# ET-USB.net
KiCad netlist of a schematic drawn in Altium Designer
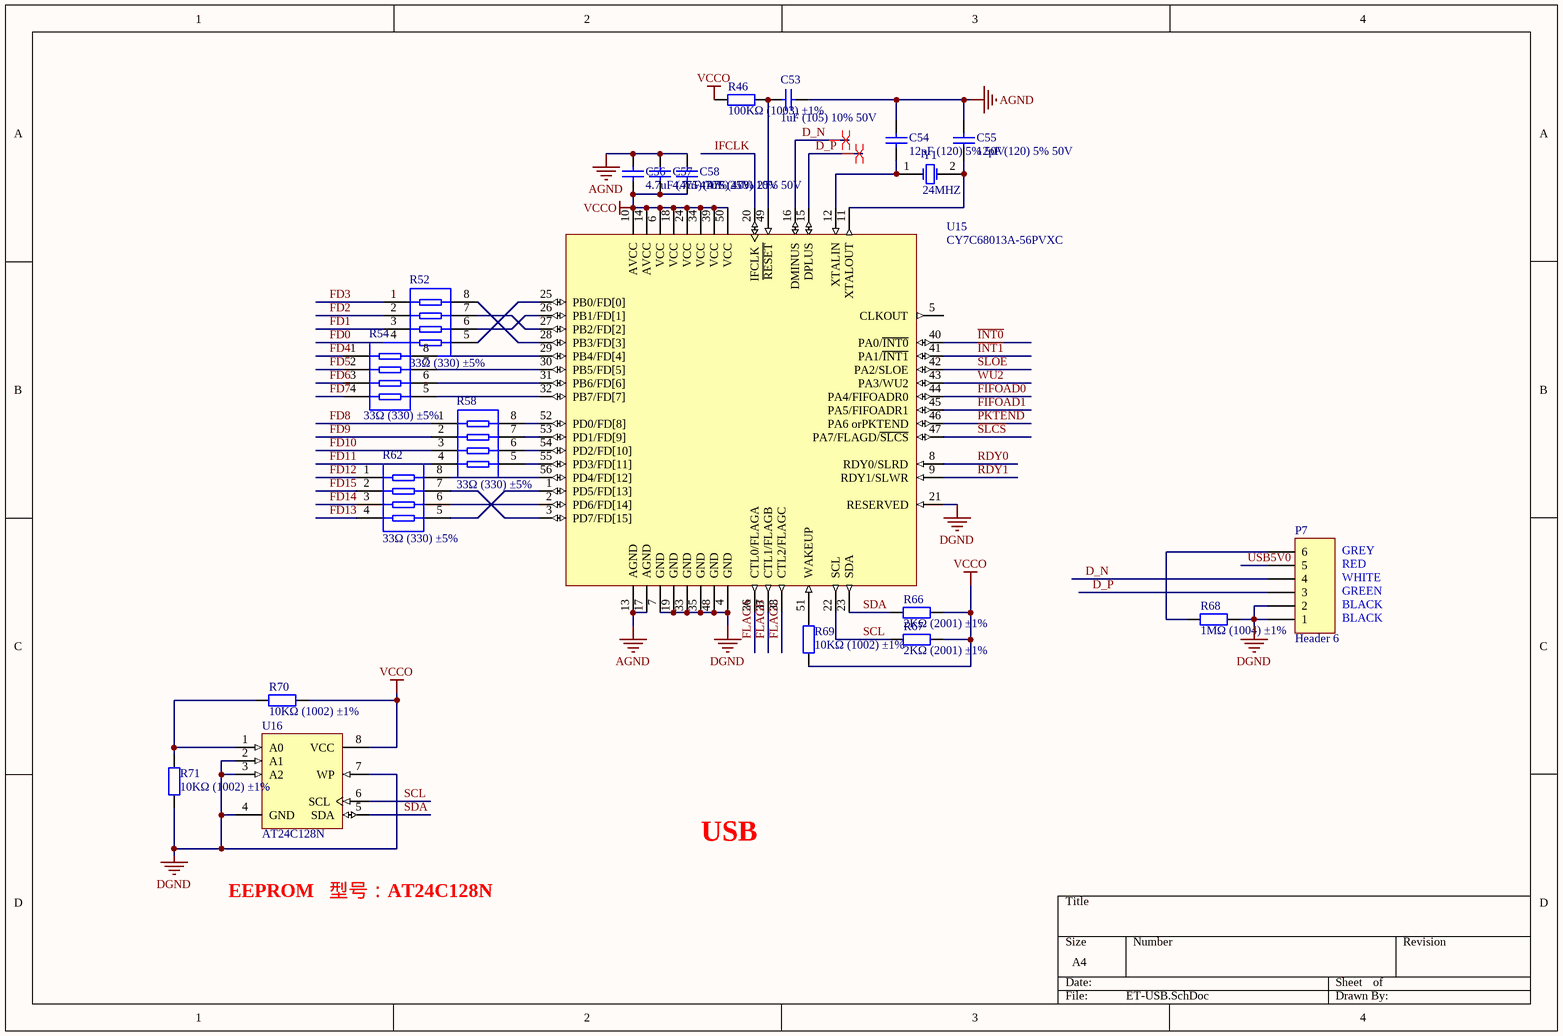
[diagram p0: ET-USB.SchDoc]

(export (version "E")
  (design (tool "Eeschema 10.0.6"))
  (components
    (comp (ref "C53")
      (value "1uF (105) 10% 50V")
      (footprint "LC-0805_C")
      (description "贴片电容")
      (libsource (lib "Miscellaneous Devices LC") (part "0805 1uF (105) 10% 50V"))
    )
    (comp (ref "C54")
      (value "12pF (120) 5% 50V")
      (footprint "LC-0805_C")
      (description "贴片电容")
      (libsource (lib "Miscellaneous Devices LC") (part "0805 12pF (120) 5% 50V"))
    )
    (comp (ref "C55")
      (value "12pF (120) 5% 50V")
      (footprint "LC-0805_C")
      (description "贴片电容")
      (libsource (lib "Miscellaneous Devices LC") (part "0805 12pF (120) 5% 50V"))
    )
    (comp (ref "C56")
      (value "4.7uF (475) 10% 25V")
      (footprint "LC-0805_C")
      (description "贴片电容")
      (libsource (lib "Miscellaneous Devices LC") (part "0805 4.7uF (475) 10% 25V"))
    )
    (comp (ref "C57")
      (value "4.7uF (475) 10% 25V")
      (footprint "LC-0805_C")
      (description "贴片电容")
      (libsource (lib "Miscellaneous Devices LC") (part "0805 4.7uF (475) 10% 25V"))
    )
    (comp (ref "C58")
      (value "47nF (473) 10% 50V")
      (footprint "LC-0805_C")
      (description "贴片电容")
      (libsource (lib "Miscellaneous Devices LC") (part "0805 47nF (473) 10% 50V"))
    )
    (comp (ref "P7")
      (value "Header 6")
      (footprint "HDR1X6")
      (description "Header, 6-Pin")
      (fields (field (name "PUBLISHER") "Altium Limited"))
      (libsource (lib "Miscellaneous Connectors") (part "Header 6"))
    )
    (comp (ref "R46")
      (value "100KΩ (1003) ±1%")
      (footprint "LC-0805_R")
      (description "贴片电阻")
      (libsource (lib "Miscellaneous Devices LC") (part "0805 100KΩ (1003) 1%"))
    )
    (comp (ref "R52")
      (value "33Ω (330) ±5%")
      (footprint "LC-0402_Rx4")
      (description "贴片排阻")
      (libsource (lib "Miscellaneous Devices LC") (part "0402*4 33Ω (330) 5%"))
    )
    (comp (ref "R54")
      (value "33Ω (330) ±5%")
      (footprint "LC-0402_Rx4")
      (description "贴片排阻")
      (libsource (lib "Miscellaneous Devices LC") (part "0402*4 33Ω (330) 5%"))
    )
    (comp (ref "R58")
      (value "33Ω (330) ±5%")
      (footprint "LC-0402_Rx4")
      (description "贴片排阻")
      (libsource (lib "Miscellaneous Devices LC") (part "0402*4 33Ω (330) 5%"))
    )
    (comp (ref "R62")
      (value "33Ω (330) ±5%")
      (footprint "LC-0402_Rx4")
      (description "贴片排阻")
      (libsource (lib "Miscellaneous Devices LC") (part "0402*4 33Ω (330) 5%"))
    )
    (comp (ref "R66")
      (value "2KΩ (2001) ±1%")
      (footprint "LC-0805_R")
      (description "贴片电阻")
      (libsource (lib "Miscellaneous Devices LC") (part "0805 2KΩ (2001) 1%"))
    )
    (comp (ref "R67")
      (value "2KΩ (2001) ±1%")
      (footprint "LC-0805_R")
      (description "贴片电阻")
      (libsource (lib "Miscellaneous Devices LC") (part "0805 2KΩ (2001) 1%"))
    )
    (comp (ref "R68")
      (value "1MΩ (1004) ±1%")
      (footprint "LC-0805_R")
      (description "贴片电阻")
      (libsource (lib "Miscellaneous Devices LC") (part "0805 1MΩ (1004) 1%"))
    )
    (comp (ref "R69")
      (value "10KΩ (1002) ±1%")
      (footprint "LC-0805_R")
      (description "贴片电阻")
      (libsource (lib "Miscellaneous Devices LC") (part "0805 10KΩ (1002) 1%"))
    )
    (comp (ref "R70")
      (value "10KΩ (1002) ±1%")
      (footprint "LC-0805_R")
      (description "贴片电阻")
      (libsource (lib "") (part "0805 10KΩ (1002) 1%_1"))
    )
    (comp (ref "R71")
      (value "10KΩ (1002) ±1%")
      (footprint "LC-0805_R")
      (description "贴片电阻")
      (libsource (lib "Miscellaneous Devices LC") (part "0805 10KΩ (1002) 1%"))
    )
    (comp (ref "U15")
      (value "CY7C68013A-56PVXC")
      (footprint "O56_N")
      (fields (field (name "PUBLISHER") "Altium Limited"))
      (libsource (lib "Cypress USB High-Speed") (part "CY7C68013A-56PVXC"))
    )
    (comp (ref "U16")
      (value "AT24C128N")
      (footprint "8P3")
      (description "1Kbit (128 x 8), 2-wire Bus Automotive Serial EEPROM with Write Protect, 2.5V, 8-Pin SOIC, Bulk")
      (fields (field (name "PUBLISHER") "Altium Limited"))
      (libsource (lib "Atmel Memory Serial EEPROM") (part "AT24C01BN-SP25-B"))
    )
    (comp (ref "Y1")
      (value "24MHZ")
      (footprint "XTAL5")
      (description "Crystal Oscillator")
      (fields (field (name "PUBLISHER") "Altium Limited"))
      (libsource (lib "晶振封装") (part "XTAL"))
    )
  )
  (nets
    (net (code "2") (name "/D_N") (class "Default")
      (node (ref "P7") (pin "4") (pinfunction "4_4") (pintype "passive"))
      (node (ref "U15") (pin "16") (pinfunction "DMINUS_16") (pintype "bidirectional"))
    )
    (net (code "3") (name "/D_P") (class "Default")
      (node (ref "P7") (pin "3") (pinfunction "3_3") (pintype "passive"))
      (node (ref "U15") (pin "15") (pinfunction "DPLUS_15") (pintype "bidirectional"))
    )
    (net (code "4") (name "/FD0") (class "Default")
      (node (ref "R52") (pin "4") (pinfunction "4_4") (pintype "passive"))
    )
    (net (code "5") (name "/FD1") (class "Default")
      (node (ref "R52") (pin "3") (pinfunction "3_3") (pintype "passive"))
    )
    (net (code "6") (name "/FD2") (class "Default")
      (node (ref "R52") (pin "2") (pinfunction "2_2") (pintype "passive"))
    )
    (net (code "7") (name "/FD3") (class "Default")
      (node (ref "R52") (pin "1") (pinfunction "1_1") (pintype "passive"))
    )
    (net (code "8") (name "/FD4") (class "Default")
      (node (ref "R54") (pin "1") (pinfunction "1_1") (pintype "passive"))
    )
    (net (code "9") (name "/FD5") (class "Default")
      (node (ref "R54") (pin "2") (pinfunction "2_2") (pintype "passive"))
    )
    (net (code "10") (name "/FD6") (class "Default")
      (node (ref "R54") (pin "3") (pinfunction "3_3") (pintype "passive"))
    )
    (net (code "11") (name "/FD7") (class "Default")
      (node (ref "R54") (pin "4") (pinfunction "4_4") (pintype "passive"))
    )
    (net (code "12") (name "/FD8") (class "Default")
      (node (ref "R58") (pin "1") (pinfunction "1_1") (pintype "passive"))
    )
    (net (code "13") (name "/FD9") (class "Default")
      (node (ref "R58") (pin "2") (pinfunction "2_2") (pintype "passive"))
    )
    (net (code "14") (name "/FD10") (class "Default")
      (node (ref "R58") (pin "3") (pinfunction "3_3") (pintype "passive"))
    )
    (net (code "15") (name "/FD11") (class "Default")
      (node (ref "R58") (pin "4") (pinfunction "4_4") (pintype "passive"))
    )
    (net (code "16") (name "/FD12") (class "Default")
      (node (ref "R62") (pin "1") (pinfunction "1_1") (pintype "passive"))
    )
    (net (code "17") (name "/FD13") (class "Default")
      (node (ref "R62") (pin "4") (pinfunction "4_4") (pintype "passive"))
    )
    (net (code "18") (name "/FD14") (class "Default")
      (node (ref "R62") (pin "3") (pinfunction "3_3") (pintype "passive"))
    )
    (net (code "19") (name "/FD15") (class "Default")
      (node (ref "R62") (pin "2") (pinfunction "2_2") (pintype "passive"))
    )
    (net (code "20") (name "/FIFOAD0") (class "Default")
      (node (ref "U15") (pin "44") (pinfunction "PA4/FIFOADR0_44") (pintype "bidirectional"))
    )
    (net (code "21") (name "/FIFOAD1") (class "Default")
      (node (ref "U15") (pin "45") (pinfunction "PA5/FIFOADR1_45") (pintype "bidirectional"))
    )
    (net (code "22") (name "/FLAGA") (class "Default")
      (node (ref "U15") (pin "36") (pinfunction "CTL0/FLAGA_36") (pintype "output"))
    )
    (net (code "23") (name "/FLAGB") (class "Default")
      (node (ref "U15") (pin "37") (pinfunction "CTL1/FLAGB_37") (pintype "output"))
    )
    (net (code "24") (name "/FLAGC") (class "Default")
      (node (ref "U15") (pin "38") (pinfunction "CTL2/FLAGC_38") (pintype "output"))
    )
    (net (code "27") (name "/IFCLK") (class "Default")
      (node (ref "U15") (pin "20") (pinfunction "IFCLK_20") (pintype "bidirectional"))
    )
    (net (code "28") (name "/PKTEND") (class "Default")
      (node (ref "U15") (pin "46") (pinfunction "PA6_orPKTEND_46") (pintype "bidirectional"))
    )
    (net (code "29") (name "/RDY0") (class "Default")
      (node (ref "U15") (pin "8") (pinfunction "RDY0/SLRD_8") (pintype "input"))
    )
    (net (code "30") (name "/RDY1") (class "Default")
      (node (ref "U15") (pin "9") (pinfunction "RDY1/SLWR_9") (pintype "input"))
    )
    (net (code "32") (name "/SCL") (class "Default")
      (node (ref "R67") (pin "1") (pinfunction "1_1") (pintype "passive"))
      (node (ref "U15") (pin "22") (pinfunction "SCL_22") (pintype "output"))
      (node (ref "U16") (pin "6") (pinfunction "SCL_6") (pintype "input"))
    )
    (net (code "33") (name "/SDA") (class "Default")
      (node (ref "R66") (pin "1") (pinfunction "1_1") (pintype "passive"))
      (node (ref "U15") (pin "23") (pinfunction "SDA_23") (pintype "output"))
      (node (ref "U16") (pin "5") (pinfunction "SDA_5") (pintype "bidirectional"))
    )
    (net (code "34") (name "/SLOE") (class "Default")
      (node (ref "U15") (pin "42") (pinfunction "PA2/SLOE_42") (pintype "bidirectional"))
    )
    (net (code "35") (name "/USB5V0") (class "Default")
      (node (ref "P7") (pin "5") (pinfunction "5_5") (pintype "passive"))
    )
    (net (code "37") (name "/WU2") (class "Default")
      (node (ref "U15") (pin "43") (pinfunction "PA3/WU2_43") (pintype "bidirectional"))
    )
    (net (code "38") (name "/~{INT0}") (class "Default")
      (node (ref "U15") (pin "40") (pinfunction "PA0/~{INT0}_40") (pintype "bidirectional"))
    )
    (net (code "39") (name "/~{INT1}") (class "Default")
      (node (ref "U15") (pin "41") (pinfunction "PA1/~{INT1}_41") (pintype "bidirectional"))
    )
    (net (code "40") (name "/~{SLCS}") (class "Default")
      (node (ref "U15") (pin "47") (pinfunction "PA7/FLAGD/~{SLCS}_47") (pintype "bidirectional"))
    )
    (net (code "41") (name "AGND") (class "Default")
      (node (ref "C53") (pin "2") (pinfunction "2_2") (pintype "passive"))
      (node (ref "C54") (pin "2") (pinfunction "2_2") (pintype "passive"))
      (node (ref "C55") (pin "2") (pinfunction "2_2") (pintype "passive"))
      (node (ref "C56") (pin "2") (pinfunction "2_2") (pintype "passive"))
      (node (ref "C57") (pin "2") (pinfunction "2_2") (pintype "passive"))
      (node (ref "C58") (pin "2") (pinfunction "2_2") (pintype "passive"))
      (node (ref "U15") (pin "13") (pinfunction "AGND_13") (pintype "power_in"))
      (node (ref "U15") (pin "17") (pinfunction "AGND_17") (pintype "power_in"))
    )
    (net (code "42") (name "DGND") (class "Default")
      (node (ref "P7") (pin "1") (pinfunction "1_1") (pintype "passive"))
      (node (ref "P7") (pin "2") (pinfunction "2_2") (pintype "passive"))
      (node (ref "R68") (pin "2") (pinfunction "2_2") (pintype "passive"))
      (node (ref "R71") (pin "1") (pinfunction "1_1") (pintype "passive"))
      (node (ref "U15") (pin "19") (pinfunction "GND_19") (pintype "power_in"))
      (node (ref "U15") (pin "21") (pinfunction "RESERVED_21") (pintype "input"))
      (node (ref "U15") (pin "33") (pinfunction "GND_33") (pintype "power_in"))
      (node (ref "U15") (pin "35") (pinfunction "GND_35") (pintype "power_in"))
      (node (ref "U15") (pin "4") (pinfunction "GND_4") (pintype "power_in"))
      (node (ref "U15") (pin "48") (pinfunction "GND_48") (pintype "power_in"))
      (node (ref "U15") (pin "7") (pinfunction "GND_7") (pintype "power_in"))
      (node (ref "U16") (pin "2") (pinfunction "A1_2") (pintype "input"))
      (node (ref "U16") (pin "3") (pinfunction "A2_3") (pintype "input"))
      (node (ref "U16") (pin "4") (pinfunction "GND_4") (pintype "power_in"))
      (node (ref "U16") (pin "7") (pinfunction "WP_7") (pintype "input"))
    )
    (net (code "43") (name "Net-(P7-Pad6)") (class "Default")
      (node (ref "P7") (pin "6") (pinfunction "6_6") (pintype "passive"))
      (node (ref "R68") (pin "1") (pinfunction "1_1") (pintype "passive"))
    )
    (net (code "44") (name "Net-(U15-PB0{slash}FD[0])") (class "Default")
      (node (ref "R52") (pin "5") (pinfunction "5_5") (pintype "passive"))
      (node (ref "U15") (pin "25") (pinfunction "PB0/FD[0]_25") (pintype "bidirectional"))
    )
    (net (code "45") (name "Net-(U15-PB1{slash}FD[1])") (class "Default")
      (node (ref "R52") (pin "6") (pinfunction "6_6") (pintype "passive"))
      (node (ref "U15") (pin "26") (pinfunction "PB1/FD[1]_26") (pintype "bidirectional"))
    )
    (net (code "46") (name "Net-(U15-PB2{slash}FD[2])") (class "Default")
      (node (ref "R52") (pin "7") (pinfunction "7_7") (pintype "passive"))
      (node (ref "U15") (pin "27") (pinfunction "PB2/FD[2]_27") (pintype "bidirectional"))
    )
    (net (code "47") (name "Net-(U15-PB3{slash}FD[3])") (class "Default")
      (node (ref "R52") (pin "8") (pinfunction "8_8") (pintype "passive"))
      (node (ref "U15") (pin "28") (pinfunction "PB3/FD[3]_28") (pintype "bidirectional"))
    )
    (net (code "48") (name "Net-(U15-PB4{slash}FD[4])") (class "Default")
      (node (ref "R54") (pin "8") (pinfunction "8_8") (pintype "passive"))
      (node (ref "U15") (pin "29") (pinfunction "PB4/FD[4]_29") (pintype "bidirectional"))
    )
    (net (code "49") (name "Net-(U15-PB5{slash}FD[5])") (class "Default")
      (node (ref "R54") (pin "7") (pinfunction "7_7") (pintype "passive"))
      (node (ref "U15") (pin "30") (pinfunction "PB5/FD[5]_30") (pintype "bidirectional"))
    )
    (net (code "50") (name "Net-(U15-PB6{slash}FD[6])") (class "Default")
      (node (ref "R54") (pin "6") (pinfunction "6_6") (pintype "passive"))
      (node (ref "U15") (pin "31") (pinfunction "PB6/FD[6]_31") (pintype "bidirectional"))
    )
    (net (code "51") (name "Net-(U15-PB7{slash}FD[7])") (class "Default")
      (node (ref "R54") (pin "5") (pinfunction "5_5") (pintype "passive"))
      (node (ref "U15") (pin "32") (pinfunction "PB7/FD[7]_32") (pintype "bidirectional"))
    )
    (net (code "52") (name "Net-(U15-PD0{slash}FD[8])") (class "Default")
      (node (ref "R58") (pin "8") (pinfunction "8_8") (pintype "passive"))
      (node (ref "U15") (pin "52") (pinfunction "PD0/FD[8]_52") (pintype "bidirectional"))
    )
    (net (code "53") (name "Net-(U15-PD1{slash}FD[9])") (class "Default")
      (node (ref "R58") (pin "7") (pinfunction "7_7") (pintype "passive"))
      (node (ref "U15") (pin "53") (pinfunction "PD1/FD[9]_53") (pintype "bidirectional"))
    )
    (net (code "54") (name "Net-(U15-PD2{slash}FD[10])") (class "Default")
      (node (ref "R58") (pin "6") (pinfunction "6_6") (pintype "passive"))
      (node (ref "U15") (pin "54") (pinfunction "PD2/FD[10]_54") (pintype "bidirectional"))
    )
    (net (code "55") (name "Net-(U15-PD3{slash}FD[11])") (class "Default")
      (node (ref "R58") (pin "5") (pinfunction "5_5") (pintype "passive"))
      (node (ref "U15") (pin "55") (pinfunction "PD3/FD[11]_55") (pintype "bidirectional"))
    )
    (net (code "56") (name "Net-(U15-PD4{slash}FD[12])") (class "Default")
      (node (ref "R62") (pin "8") (pinfunction "8_8") (pintype "passive"))
      (node (ref "U15") (pin "56") (pinfunction "PD4/FD[12]_56") (pintype "bidirectional"))
    )
    (net (code "57") (name "Net-(U15-PD5{slash}FD[13])") (class "Default")
      (node (ref "R62") (pin "5") (pinfunction "5_5") (pintype "passive"))
      (node (ref "U15") (pin "1") (pinfunction "PD5/FD[13]_1") (pintype "bidirectional"))
    )
    (net (code "58") (name "Net-(U15-PD6{slash}FD[14])") (class "Default")
      (node (ref "R62") (pin "6") (pinfunction "6_6") (pintype "passive"))
      (node (ref "U15") (pin "2") (pinfunction "PD6/FD[14]_2") (pintype "bidirectional"))
    )
    (net (code "59") (name "Net-(U15-PD7{slash}FD[15])") (class "Default")
      (node (ref "R62") (pin "7") (pinfunction "7_7") (pintype "passive"))
      (node (ref "U15") (pin "3") (pinfunction "PD7/FD[15]_3") (pintype "bidirectional"))
    )
    (net (code "60") (name "Net-(U15-WAKEUP)") (class "Default")
      (node (ref "R69") (pin "2") (pinfunction "2_2") (pintype "passive"))
      (node (ref "U15") (pin "51") (pinfunction "WAKEUP_51") (pintype "input"))
    )
    (net (code "61") (name "Net-(U15-XTALIN)") (class "Default")
      (node (ref "C54") (pin "1") (pinfunction "1_1") (pintype "passive"))
      (node (ref "U15") (pin "12") (pinfunction "XTALIN_12") (pintype "input"))
      (node (ref "Y1") (pin "1") (pinfunction "OSC1_1") (pintype "passive"))
    )
    (net (code "62") (name "Net-(U15-XTALOUT)") (class "Default")
      (node (ref "C55") (pin "1") (pinfunction "1_1") (pintype "passive"))
      (node (ref "U15") (pin "11") (pinfunction "XTALOUT_11") (pintype "output"))
      (node (ref "Y1") (pin "2") (pinfunction "OSC2_2") (pintype "passive"))
    )
    (net (code "63") (name "Net-(U15-~{RESET})") (class "Default")
      (node (ref "C53") (pin "1") (pinfunction "1_1") (pintype "passive"))
      (node (ref "R46") (pin "2") (pinfunction "2_2") (pintype "passive"))
      (node (ref "U15") (pin "49") (pinfunction "~{RESET}_49") (pintype "input"))
    )
    (net (code "64") (name "Net-(U16-A0)") (class "Default")
      (node (ref "R70") (pin "1") (pinfunction "1_1") (pintype "passive"))
      (node (ref "R71") (pin "2") (pinfunction "2_2") (pintype "passive"))
      (node (ref "U16") (pin "1") (pinfunction "A0_1") (pintype "input"))
    )
    (net (code "65") (name "VCCO") (class "Default")
      (node (ref "C56") (pin "1") (pinfunction "1_1") (pintype "passive"))
      (node (ref "C57") (pin "1") (pinfunction "1_1") (pintype "passive"))
      (node (ref "C58") (pin "1") (pinfunction "1_1") (pintype "passive"))
      (node (ref "R46") (pin "1") (pinfunction "1_1") (pintype "passive"))
      (node (ref "R66") (pin "2") (pinfunction "2_2") (pintype "passive"))
      (node (ref "R67") (pin "2") (pinfunction "2_2") (pintype "passive"))
      (node (ref "R69") (pin "1") (pinfunction "1_1") (pintype "passive"))
      (node (ref "R70") (pin "2") (pinfunction "2_2") (pintype "passive"))
      (node (ref "U15") (pin "10") (pinfunction "AVCC_10") (pintype "power_in"))
      (node (ref "U15") (pin "14") (pinfunction "AVCC_14") (pintype "power_in"))
      (node (ref "U15") (pin "18") (pinfunction "VCC_18") (pintype "power_in"))
      (node (ref "U15") (pin "24") (pinfunction "VCC_24") (pintype "power_in"))
      (node (ref "U15") (pin "34") (pinfunction "VCC_34") (pintype "power_in"))
      (node (ref "U15") (pin "39") (pinfunction "VCC_39") (pintype "power_in"))
      (node (ref "U15") (pin "50") (pinfunction "VCC_50") (pintype "power_in"))
      (node (ref "U15") (pin "6") (pinfunction "VCC_6") (pintype "power_in"))
      (node (ref "U16") (pin "8") (pinfunction "VCC_8") (pintype "power_in"))
    )
    (net (code "66") (name "unconnected-(U15-CLKOUT-Pad5)") (class "Default")
      (node (ref "U15") (pin "5") (pinfunction "CLKOUT_5") (pintype "output"))
    )
  )
)
